# Fans.net
KiCad netlist of a schematic drawn in Altium Designer
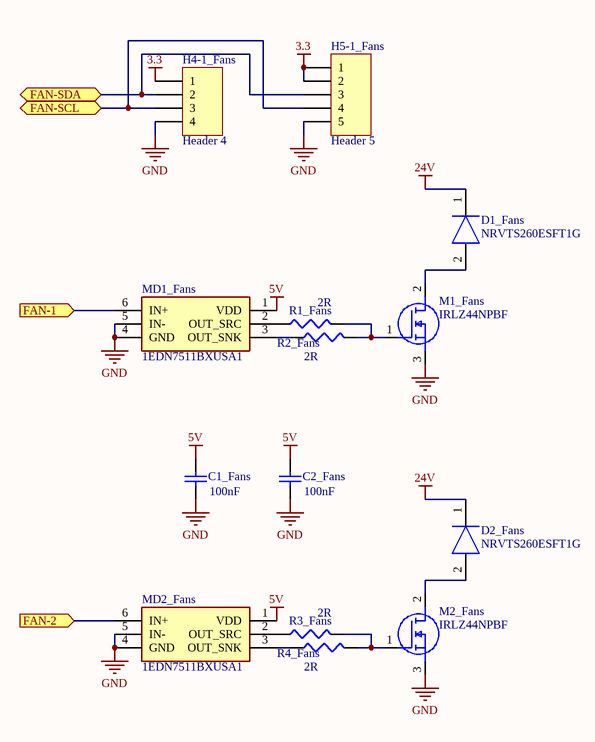
[diagram p0: Fans.SchDoc]

(export (version "E")
  (design (tool "Eeschema 10.0.6"))
  (components
    (comp (ref "C1_Fans")
      (value "100nF")
      (footprint "1608[0603]")
      (description "Capacitor (Semiconductor SIM Model)")
      (fields (field (name "Comment") "Cap Semi") (field (name "PUBLISHER") "Altium Limited"))
      (libsource (lib "Miscellaneous Devices") (part "Cap Semi"))
    )
    (comp (ref "C2_Fans")
      (value "100nF")
      (footprint "1608[0603]")
      (description "Capacitor (Semiconductor SIM Model)")
      (fields (field (name "Comment") "Cap Semi") (field (name "PUBLISHER") "Altium Limited"))
      (libsource (lib "Miscellaneous Devices") (part "Cap Semi"))
    )
    (comp (ref "D1_Fans")
      (value "NRVTS260ESFT1G")
      (footprint "LX1-Teensy:SODFL3616X98N")
      (description "Diode")
      (fields
        (field (name "MOUSER PART NUMBER") "863-NRVTS260ESFT1G")
        (field (name "RS PART NUMBER") "8673243P")
      )
      (libsource (lib "LX1-Teensy") (part "NRVTS260ESFT1G"))
    )
    (comp (ref "D2_Fans")
      (value "NRVTS260ESFT1G")
      (footprint "LX1-Teensy:SODFL3616X98N")
      (description "Diode")
      (fields
        (field (name "MOUSER PART NUMBER") "863-NRVTS260ESFT1G")
        (field (name "RS PART NUMBER") "8673243P")
      )
      (libsource (lib "LX1-Teensy") (part "NRVTS260ESFT1G"))
    )
    (comp (ref "H4-1_Fans")
      (value "Header 4")
      (footprint "HDR1X4")
      (description "Header, 4-Pin")
      (fields (field (name "PUBLISHER") "Altium Limited"))
      (libsource (lib "Miscellaneous Connectors") (part "Header 4"))
    )
    (comp (ref "H5-1_Fans")
      (value "Header 5")
      (footprint "HDR1X5")
      (description "Header, 5-Pin")
      (fields (field (name "PUBLISHER") "Altium Limited"))
      (libsource (lib "Miscellaneous Connectors") (part "Header 5"))
    )
    (comp (ref "M1_Fans")
      (value "IRLZ44NPBF")
      (footprint "LX1-Fans:TO254P469X1042X1967-3P")
      (description "MOSFET (N-Channel)")
      (fields (field (name "MOUSER PART NUMBER") "942-IRLZ44NPBF") (field (name "RS PART NUMBER") "5410086P"))
      (libsource (lib "LX1-Fans") (part "IRLZ44NPBF"))
    )
    (comp (ref "M2_Fans")
      (value "IRLZ44NPBF")
      (footprint "LX1-Fans:TO254P469X1042X1967-3P")
      (description "MOSFET (N-Channel)")
      (fields (field (name "MOUSER PART NUMBER") "942-IRLZ44NPBF") (field (name "RS PART NUMBER") "5410086P"))
      (libsource (lib "LX1-Fans") (part "IRLZ44NPBF"))
    )
    (comp (ref "MD1_Fans")
      (value "1EDN7511BXUSA1")
      (footprint "LX1-Fans:SOT95P280X145-6N")
      (description "Integrated Circuit")
      (fields (field (name "MOUSER PART NUMBER") "726-1EDN7511BXUSA1"))
      (libsource (lib "LX1-Fans") (part "1EDN7511BXUSA1"))
    )
    (comp (ref "MD2_Fans")
      (value "1EDN7511BXUSA1")
      (footprint "LX1-Fans:SOT95P280X145-6N")
      (description "Integrated Circuit")
      (fields (field (name "MOUSER PART NUMBER") "726-1EDN7511BXUSA1"))
      (libsource (lib "LX1-Fans") (part "1EDN7511BXUSA1"))
    )
    (comp (ref "R1_Fans")
      (value "2R")
      (footprint "J1-0603")
      (description "Resistor")
      (fields (field (name "Comment") "Res3") (field (name "PUBLISHER") "Altium Limited"))
      (libsource (lib "Miscellaneous Devices") (part "Res3"))
    )
    (comp (ref "R2_Fans")
      (value "2R")
      (footprint "J1-0603")
      (description "Resistor")
      (fields (field (name "Comment") "Res3") (field (name "PUBLISHER") "Altium Limited"))
      (libsource (lib "Miscellaneous Devices") (part "Res3"))
    )
    (comp (ref "R3_Fans")
      (value "2R")
      (footprint "J1-0603")
      (description "Resistor")
      (fields (field (name "Comment") "Res3") (field (name "PUBLISHER") "Altium Limited"))
      (libsource (lib "Miscellaneous Devices") (part "Res3"))
    )
    (comp (ref "R4_Fans")
      (value "2R")
      (footprint "J1-0603")
      (description "Resistor")
      (fields (field (name "Comment") "Res3") (field (name "PUBLISHER") "Altium Limited"))
      (libsource (lib "Miscellaneous Devices") (part "Res3"))
    )
  )
  (nets
    (net (code "1") (name "/FAN-1") (class "Default")
      (node (ref "MD1_Fans") (pin "6") (pinfunction "IN+_6") (pintype "passive"))
    )
    (net (code "2") (name "/FAN-2") (class "Default")
      (node (ref "MD2_Fans") (pin "6") (pinfunction "IN+_6") (pintype "passive"))
    )
    (net (code "3") (name "/FAN-SCL") (class "Default")
      (node (ref "H4-1_Fans") (pin "3") (pinfunction "3_3") (pintype "passive"))
      (node (ref "H5-1_Fans") (pin "4") (pinfunction "4_4") (pintype "passive"))
    )
    (net (code "4") (name "/FAN-SDA") (class "Default")
      (node (ref "H4-1_Fans") (pin "2") (pinfunction "2_2") (pintype "passive"))
      (node (ref "H5-1_Fans") (pin "3") (pinfunction "3_3") (pintype "passive"))
    )
    (net (code "5") (name "3.3") (class "Default")
      (node (ref "H4-1_Fans") (pin "1") (pinfunction "1_1") (pintype "passive"))
      (node (ref "H5-1_Fans") (pin "1") (pinfunction "1_1") (pintype "passive"))
      (node (ref "H5-1_Fans") (pin "2") (pinfunction "2_2") (pintype "passive"))
    )
    (net (code "6") (name "5V") (class "Default")
      (node (ref "C1_Fans") (pin "2") (pinfunction "2_2") (pintype "passive"))
      (node (ref "C2_Fans") (pin "2") (pinfunction "2_2") (pintype "passive"))
      (node (ref "MD1_Fans") (pin "1") (pinfunction "VDD_1") (pintype "passive"))
      (node (ref "MD2_Fans") (pin "1") (pinfunction "VDD_1") (pintype "passive"))
    )
    (net (code "7") (name "24V") (class "Default")
      (node (ref "D1_Fans") (pin "1") (pinfunction "K_1") (pintype "passive"))
      (node (ref "D2_Fans") (pin "1") (pinfunction "K_1") (pintype "passive"))
    )
    (net (code "8") (name "GND") (class "Default")
      (node (ref "C1_Fans") (pin "1") (pinfunction "1_1") (pintype "passive"))
      (node (ref "C2_Fans") (pin "1") (pinfunction "1_1") (pintype "passive"))
      (node (ref "H4-1_Fans") (pin "4") (pinfunction "4_4") (pintype "passive"))
      (node (ref "H5-1_Fans") (pin "5") (pinfunction "5_5") (pintype "passive"))
      (node (ref "M1_Fans") (pin "3") (pinfunction "S_3") (pintype "passive"))
      (node (ref "M2_Fans") (pin "3") (pinfunction "S_3") (pintype "passive"))
      (node (ref "MD1_Fans") (pin "4") (pinfunction "GND_4") (pintype "passive"))
      (node (ref "MD1_Fans") (pin "5") (pinfunction "IN-_5") (pintype "passive"))
      (node (ref "MD2_Fans") (pin "4") (pinfunction "GND_4") (pintype "passive"))
      (node (ref "MD2_Fans") (pin "5") (pinfunction "IN-_5") (pintype "passive"))
    )
    (net (code "9") (name "Net-(D1_Fans-A)") (class "Default")
      (node (ref "D1_Fans") (pin "2") (pinfunction "A_2") (pintype "passive"))
      (node (ref "M1_Fans") (pin "2") (pinfunction "D_2") (pintype "passive"))
    )
    (net (code "10") (name "Net-(D2_Fans-A)") (class "Default")
      (node (ref "D2_Fans") (pin "2") (pinfunction "A_2") (pintype "passive"))
      (node (ref "M2_Fans") (pin "2") (pinfunction "D_2") (pintype "passive"))
    )
    (net (code "11") (name "Net-(M1_Fans-G)") (class "Default")
      (node (ref "M1_Fans") (pin "1") (pinfunction "G_1") (pintype "passive"))
      (node (ref "R1_Fans") (pin "2") (pinfunction "2_2") (pintype "passive"))
      (node (ref "R2_Fans") (pin "2") (pinfunction "2_2") (pintype "passive"))
    )
    (net (code "12") (name "Net-(M2_Fans-G)") (class "Default")
      (node (ref "M2_Fans") (pin "1") (pinfunction "G_1") (pintype "passive"))
      (node (ref "R3_Fans") (pin "2") (pinfunction "2_2") (pintype "passive"))
      (node (ref "R4_Fans") (pin "2") (pinfunction "2_2") (pintype "passive"))
    )
    (net (code "13") (name "Net-(MD1_Fans-OUT_SNK)") (class "Default")
      (node (ref "MD1_Fans") (pin "3") (pinfunction "OUT_SNK_3") (pintype "passive"))
      (node (ref "R2_Fans") (pin "1") (pinfunction "1_1") (pintype "passive"))
    )
    (net (code "14") (name "Net-(MD1_Fans-OUT_SRC)") (class "Default")
      (node (ref "MD1_Fans") (pin "2") (pinfunction "OUT_SRC_2") (pintype "passive"))
      (node (ref "R1_Fans") (pin "1") (pinfunction "1_1") (pintype "passive"))
    )
    (net (code "15") (name "Net-(MD2_Fans-OUT_SNK)") (class "Default")
      (node (ref "MD2_Fans") (pin "3") (pinfunction "OUT_SNK_3") (pintype "passive"))
      (node (ref "R4_Fans") (pin "1") (pinfunction "1_1") (pintype "passive"))
    )
    (net (code "16") (name "Net-(MD2_Fans-OUT_SRC)") (class "Default")
      (node (ref "MD2_Fans") (pin "2") (pinfunction "OUT_SRC_2") (pintype "passive"))
      (node (ref "R3_Fans") (pin "1") (pinfunction "1_1") (pintype "passive"))
    )
  )
)
